# VAST.net
KiCad netlist of a schematic drawn in EAGLE
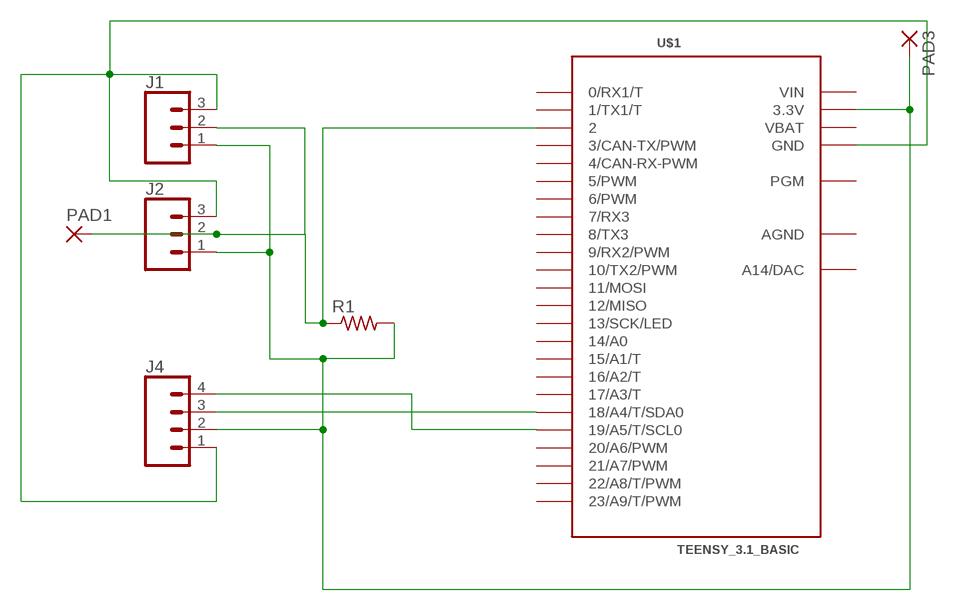
[diagram p0: schematic, sheet 1]

(export (version "E")
  (design (tool "Eeschema 10.0.6"))
  (components
    (comp (ref "J1")
      (value "CONN_03POLAR_LOCK")
      (footprint "eagle-import:MOLEX-1X3_LOCK")
      (libsource (lib "eagle-import") (part "CONN_03POLAR_LOCK"))
    )
    (comp (ref "J2")
      (value "CONN_03POLAR_LOCK")
      (footprint "eagle-import:MOLEX-1X3_LOCK")
      (libsource (lib "eagle-import") (part "CONN_03POLAR_LOCK"))
    )
    (comp (ref "J4")
      (value "CONN_04POLAR")
      (footprint "eagle-import:MOLEX-1X4")
      (libsource (lib "eagle-import") (part "CONN_04POLAR"))
    )
    (comp (ref "PAD1")
      (value "SMD5")
      (footprint "eagle-import:SMD2,54-5,08")
      (libsource (lib "eagle-import") (part "SMD5"))
    )
    (comp (ref "PAD3")
      (value "SMD5")
      (footprint "eagle-import:SMD2,54-5,08")
      (libsource (lib "eagle-import") (part "SMD5"))
    )
    (comp (ref "R1")
      (value "ADAFRUIT_R-US_0207/10")
      (footprint "eagle-import:ADAFRUIT_0207_10")
      (libsource (lib "eagle-import") (part "ADAFRUIT_R-US_0207/10"))
    )
    (comp (ref "U$1")
      (value "TEENSY_3.1_BASIC")
      (footprint "eagle-import:TEENSY_3.1_BASIC")
      (libsource (lib "eagle-import") (part "TEENSY_3.1_BASIC"))
    )
  )
  (nets
    (net (code "1") (name "/AGND") (class "Default")
      (node (ref "U$1") (pin "AGND") (pinfunction "AGND_AGND") (pintype "power_in"))
    )
    (net (code "2") (name "/VBAT") (class "Default")
      (node (ref "U$1") (pin "VBAT") (pinfunction "VBAT_VBAT") (pintype "power_in"))
    )
    (net (code "3") (name "/VIN") (class "Default")
      (node (ref "U$1") (pin "VIN") (pinfunction "VIN_VIN") (pintype "power_in"))
    )
    (net (code "4") (name "Net-(J1-Pad3)") (class "Default")
      (node (ref "J1") (pin "3") (pinfunction "3_3") (pintype "passive"))
      (node (ref "J2") (pin "3") (pinfunction "3_3") (pintype "passive"))
      (node (ref "J4") (pin "1") (pinfunction "1_1") (pintype "passive"))
      (node (ref "U$1") (pin "GND") (pinfunction "GND_GND") (pintype "power_in"))
      (node (ref "U$1") (pin "GND1") (pinfunction "GND_GND1") (pintype "power_in"))
    )
    (net (code "5") (name "Net-(PAD1-P)") (class "Default")
      (node (ref "J1") (pin "2") (pinfunction "2_2") (pintype "passive"))
      (node (ref "J2") (pin "2") (pinfunction "2_2") (pintype "passive"))
      (node (ref "PAD1") (pin "1") (pinfunction "P_1") (pintype "passive"))
      (node (ref "R1") (pin "1") (pinfunction "1_1") (pintype "passive"))
      (node (ref "U$1") (pin "2") (pinfunction "2_2") (pintype "bidirectional"))
    )
    (net (code "6") (name "Net-(PAD3-P)") (class "Default")
      (node (ref "J1") (pin "1") (pinfunction "1_1") (pintype "passive"))
      (node (ref "J2") (pin "1") (pinfunction "1_1") (pintype "passive"))
      (node (ref "J4") (pin "2") (pinfunction "2_2") (pintype "passive"))
      (node (ref "PAD3") (pin "1") (pinfunction "P_1") (pintype "passive"))
      (node (ref "R1") (pin "2") (pinfunction "2_2") (pintype "passive"))
      (node (ref "U$1") (pin "3.3V") (pinfunction "3.3V_3.3V") (pintype "power_in"))
      (node (ref "U$1") (pin "3.3V1") (pinfunction "3.3V_3.3V1") (pintype "power_in"))
    )
    (net (code "7") (name "Net-(U$1-18{slash}A4{slash}T{slash}SDA0)") (class "Default")
      (node (ref "J4") (pin "3") (pinfunction "3_3") (pintype "passive"))
      (node (ref "U$1") (pin "18/A4") (pinfunction "18/A4/T/SDA0_18/A4") (pintype "bidirectional"))
    )
    (net (code "8") (name "Net-(U$1-19{slash}A5{slash}T{slash}SCL0)") (class "Default")
      (node (ref "J4") (pin "4") (pinfunction "4_4") (pintype "passive"))
      (node (ref "U$1") (pin "19/A5") (pinfunction "19/A5/T/SCL0_19/A5") (pintype "bidirectional"))
    )
    (net (code "9") (name "unconnected-(U$1-0{slash}RX1{slash}T-Pad0)") (class "Default")
      (node (ref "U$1") (pin "0") (pinfunction "0/RX1/T_0") (pintype "bidirectional"))
    )
    (net (code "10") (name "unconnected-(U$1-1{slash}TX1{slash}T-Pad1)") (class "Default")
      (node (ref "U$1") (pin "1") (pinfunction "1/TX1/T_1") (pintype "bidirectional"))
    )
    (net (code "11") (name "unconnected-(U$1-3{slash}CAN-TX{slash}PWM-Pad3)") (class "Default")
      (node (ref "U$1") (pin "3") (pinfunction "3/CAN-TX/PWM_3") (pintype "bidirectional"))
    )
    (net (code "12") (name "unconnected-(U$1-4{slash}CAN-RX-PWM-Pad4)") (class "Default")
      (node (ref "U$1") (pin "4") (pinfunction "4/CAN-RX-PWM_4") (pintype "bidirectional"))
    )
    (net (code "13") (name "unconnected-(U$1-5{slash}PWM-Pad5)") (class "Default")
      (node (ref "U$1") (pin "5") (pinfunction "5/PWM_5") (pintype "bidirectional"))
    )
    (net (code "14") (name "unconnected-(U$1-6{slash}PWM-Pad6)") (class "Default")
      (node (ref "U$1") (pin "6") (pinfunction "6/PWM_6") (pintype "bidirectional"))
    )
    (net (code "15") (name "unconnected-(U$1-7{slash}RX3-Pad7)") (class "Default")
      (node (ref "U$1") (pin "7") (pinfunction "7/RX3_7") (pintype "bidirectional"))
    )
    (net (code "16") (name "unconnected-(U$1-8{slash}TX3-Pad8)") (class "Default")
      (node (ref "U$1") (pin "8") (pinfunction "8/TX3_8") (pintype "bidirectional"))
    )
    (net (code "17") (name "unconnected-(U$1-9{slash}RX2{slash}PWM-Pad9)") (class "Default")
      (node (ref "U$1") (pin "9") (pinfunction "9/RX2/PWM_9") (pintype "bidirectional"))
    )
    (net (code "18") (name "unconnected-(U$1-10{slash}TX2{slash}PWM-Pad10)") (class "Default")
      (node (ref "U$1") (pin "10") (pinfunction "10/TX2/PWM_10") (pintype "bidirectional"))
    )
    (net (code "19") (name "unconnected-(U$1-11{slash}MOSI-Pad11)") (class "Default")
      (node (ref "U$1") (pin "11") (pinfunction "11/MOSI_11") (pintype "bidirectional"))
    )
    (net (code "20") (name "unconnected-(U$1-12{slash}MISO-Pad12)") (class "Default")
      (node (ref "U$1") (pin "12") (pinfunction "12/MISO_12") (pintype "bidirectional"))
    )
    (net (code "21") (name "unconnected-(U$1-13{slash}SCK{slash}LED-Pad13)") (class "Default")
      (node (ref "U$1") (pin "13") (pinfunction "13/SCK/LED_13") (pintype "bidirectional"))
    )
    (net (code "22") (name "unconnected-(U$1-15{slash}A1{slash}T-Pad15{slash}A1)") (class "Default")
      (node (ref "U$1") (pin "15/A1") (pinfunction "15/A1/T_15/A1") (pintype "bidirectional"))
    )
    (net (code "23") (name "unconnected-(U$1-16{slash}A2{slash}T-Pad16{slash}A2)") (class "Default")
      (node (ref "U$1") (pin "16/A2") (pinfunction "16/A2/T_16/A2") (pintype "bidirectional"))
    )
    (net (code "24") (name "unconnected-(U$1-17{slash}A3{slash}T-Pad17{slash}A3)") (class "Default")
      (node (ref "U$1") (pin "17/A3") (pinfunction "17/A3/T_17/A3") (pintype "bidirectional"))
    )
    (net (code "25") (name "unconnected-(U$1-20{slash}A6{slash}PWM-Pad20{slash}A6)") (class "Default")
      (node (ref "U$1") (pin "20/A6") (pinfunction "20/A6/PWM_20/A6") (pintype "bidirectional"))
    )
    (net (code "26") (name "unconnected-(U$1-21{slash}A7{slash}PWM-Pad21{slash}A7)") (class "Default")
      (node (ref "U$1") (pin "21/A7") (pinfunction "21/A7/PWM_21/A7") (pintype "bidirectional"))
    )
    (net (code "27") (name "unconnected-(U$1-22{slash}A8{slash}T{slash}PWM-Pad22{slash}A8)") (class "Default")
      (node (ref "U$1") (pin "22/A8") (pinfunction "22/A8/T/PWM_22/A8") (pintype "bidirectional"))
    )
    (net (code "28") (name "unconnected-(U$1-23{slash}A9{slash}T{slash}PWM-Pad23{slash}A9)") (class "Default")
      (node (ref "U$1") (pin "23/A9") (pinfunction "23/A9/T/PWM_23/A9") (pintype "bidirectional"))
    )
    (net (code "29") (name "unconnected-(U$1-A14{slash}DAC-PadA14)") (class "Default")
      (node (ref "U$1") (pin "A14") (pinfunction "A14/DAC_A14") (pintype "bidirectional"))
    )
    (net (code "30") (name "unconnected-(U$1-Pad14{slash}A0)") (class "Default")
      (node (ref "U$1") (pin "14/A0") (pinfunction "14/A0_14/A0") (pintype "bidirectional"))
    )
    (net (code "31") (name "unconnected-(U$1-PadPGM)") (class "Default")
      (node (ref "U$1") (pin "PGM") (pinfunction "PGM_PGM") (pintype "bidirectional"))
    )
  )
)
